# design.net
KiCad netlist of a schematic drawn in Altium Designer
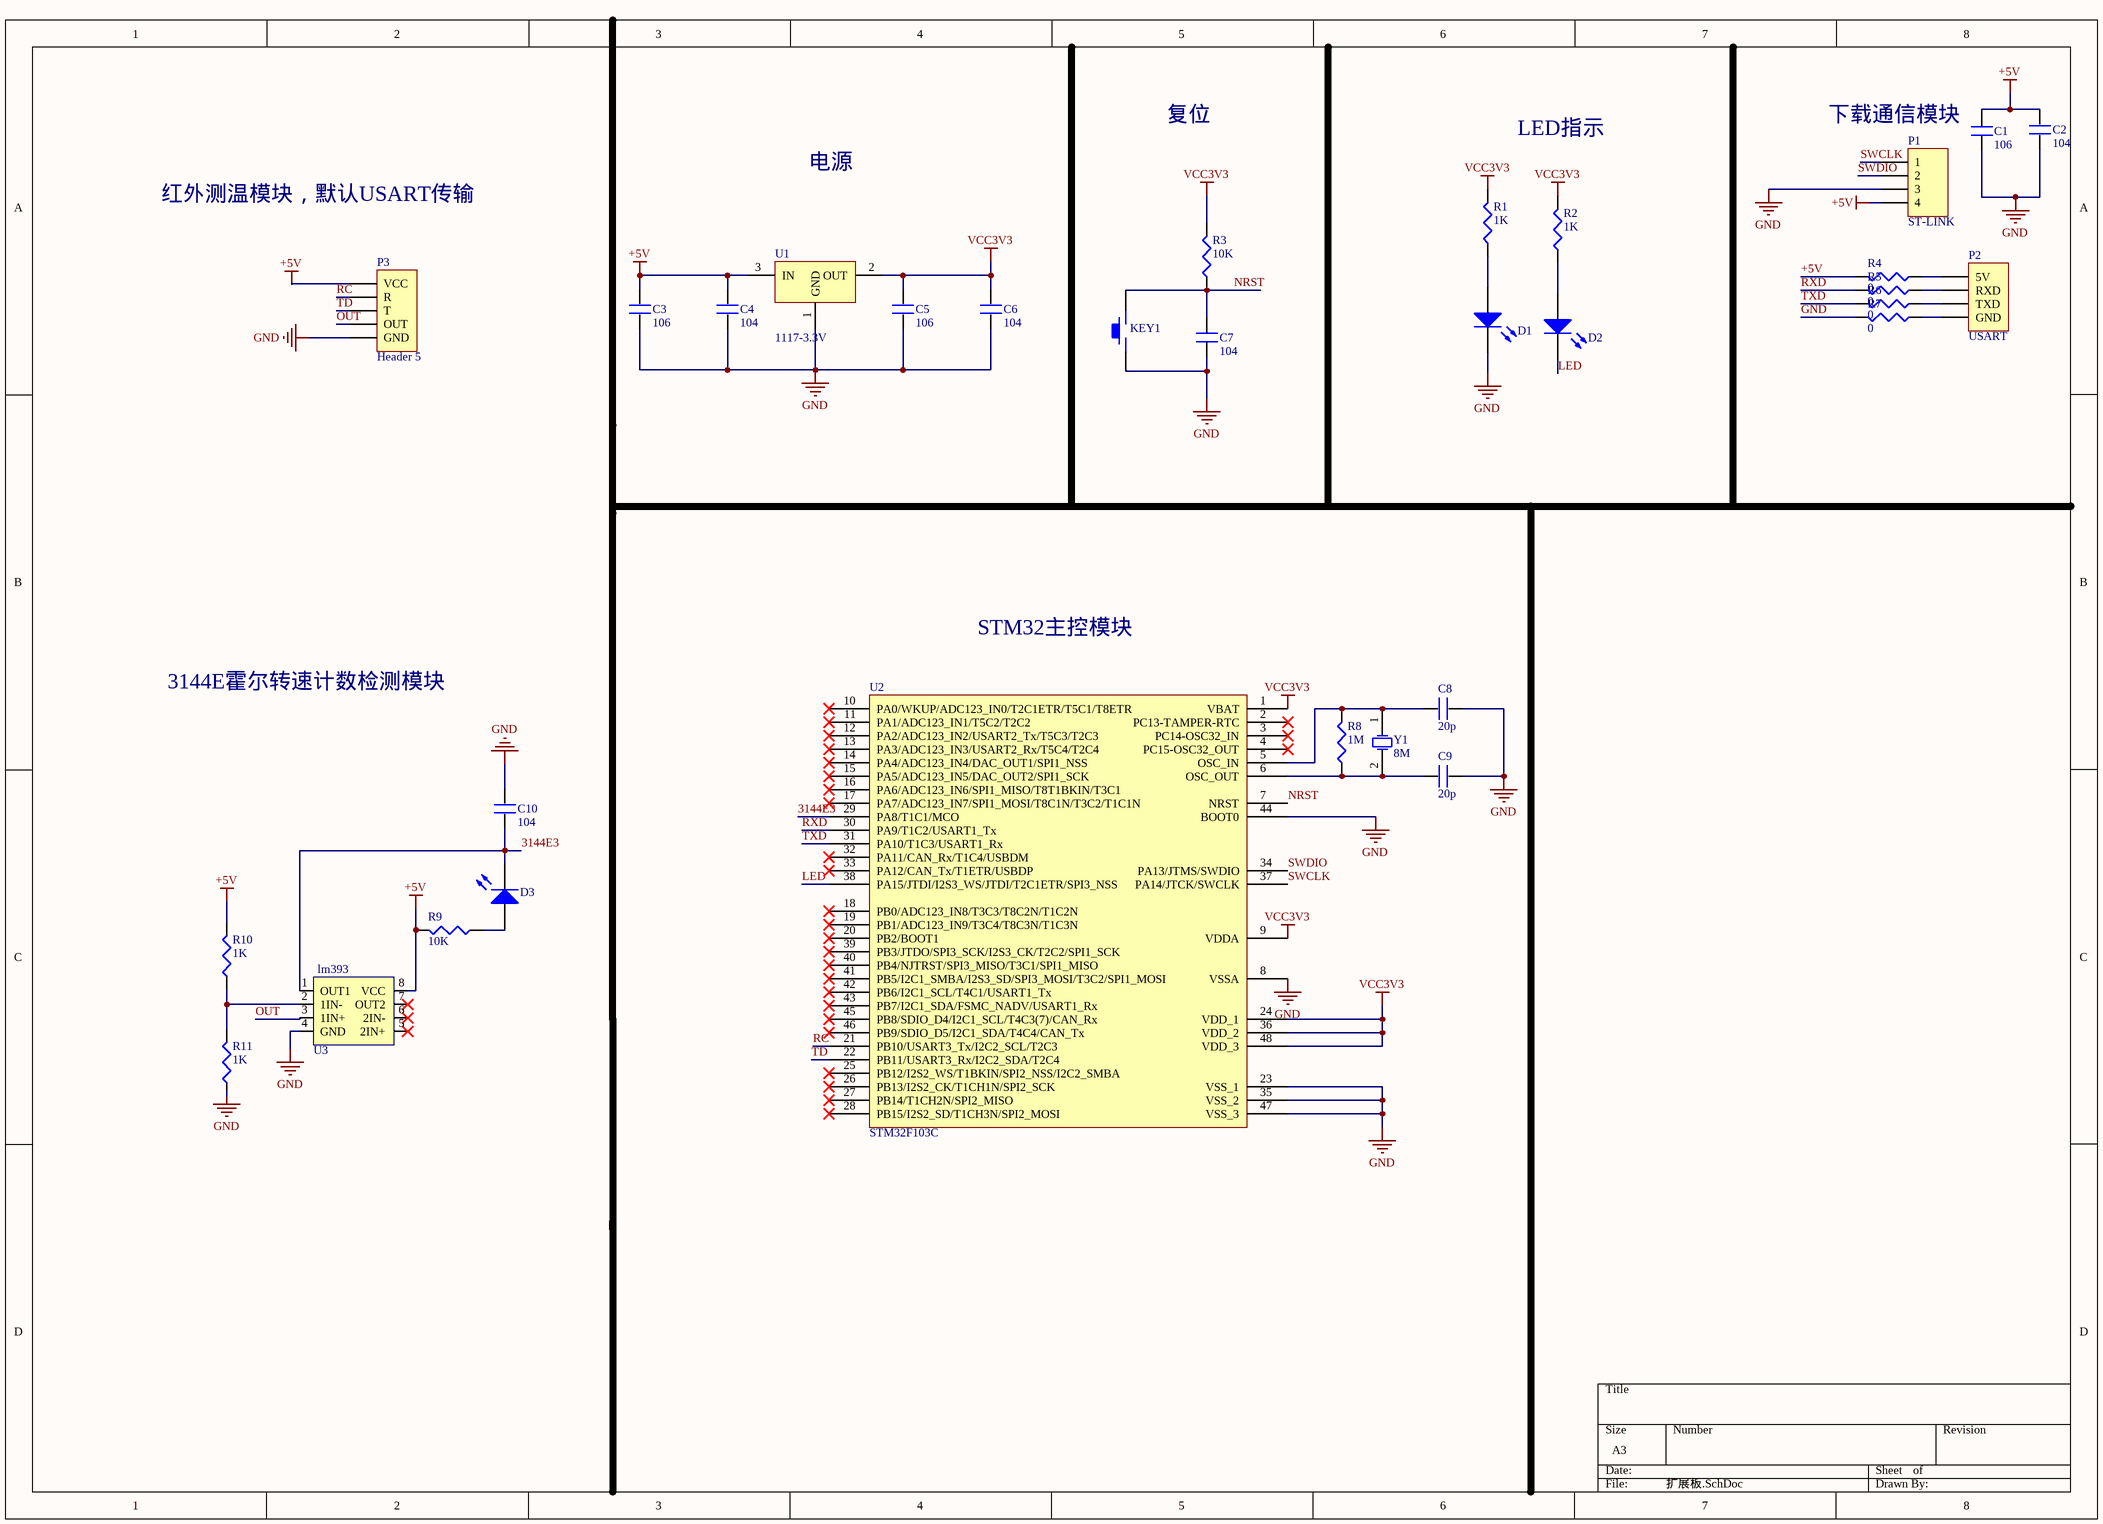
[diagram p0: 扩展板.SchDoc]

(export (version "E")
  (design (tool "Eeschema 10.0.6"))
  (components
    (comp (ref "C1")
      (value "106")
      (footprint "C0603(1608)")
      (libsource (lib "Uncle_Liu") (part "C_无极性_0603"))
    )
    (comp (ref "C2")
      (value "104")
      (footprint "C0603(1608)")
      (libsource (lib "Uncle_Liu") (part "C_无极性_0603"))
    )
    (comp (ref "C3")
      (value "106")
      (footprint "C0603(1608)")
      (libsource (lib "Uncle_Liu") (part "C_无极性_0603"))
    )
    (comp (ref "C4")
      (value "104")
      (footprint "C0603(1608)")
      (libsource (lib "Uncle_Liu") (part "C_无极性_0603"))
    )
    (comp (ref "C5")
      (value "106")
      (footprint "C0603(1608)")
      (libsource (lib "Uncle_Liu") (part "C_无极性_0603"))
    )
    (comp (ref "C6")
      (value "104")
      (footprint "C0603(1608)")
      (libsource (lib "Uncle_Liu") (part "C_无极性_0603"))
    )
    (comp (ref "C7")
      (value "104")
      (footprint "C0603(1608)")
      (libsource (lib "Uncle_Liu") (part "C_无极性_0603"))
    )
    (comp (ref "C8")
      (value "20p")
      (footprint "C0603(1608)")
      (libsource (lib "Uncle_Liu") (part "C_无极性_0603"))
    )
    (comp (ref "C9")
      (value "20p")
      (footprint "C0603(1608)")
      (libsource (lib "Uncle_Liu") (part "C_无极性_0603"))
    )
    (comp (ref "C10")
      (value "104")
      (footprint "C0603(1608)")
      (libsource (lib "Uncle_Liu") (part "C_无极性_0603"))
    )
    (comp (ref "D1")
      (value "LED0603")
      (footprint "LED_0805")
      (description "发光二极管")
      (fields (field (name "PUBLISHER") "Altium Limited"))
      (libsource (lib "Uncle_Liu") (part "LED0603"))
    )
    (comp (ref "D2")
      (value "LED0603")
      (footprint "LED_0805")
      (description "发光二极管")
      (fields (field (name "PUBLISHER") "Altium Limited"))
      (libsource (lib "Uncle_Liu") (part "LED0603"))
    )
    (comp (ref "D3")
      (value "LED0603")
      (footprint "LED_0805")
      (description "发光二极管")
      (fields (field (name "PUBLISHER") "Altium Limited"))
      (libsource (lib "Uncle_Liu") (part "LED0603"))
    )
    (comp (ref "KEY1") (value "KEY_M") (footprint "贴片按键") (libsource (lib "Uncle_Liu") (part "KEY_M")))
    (comp (ref "P1")
      (value "ST-LINK")
      (footprint "HDR1X4")
      (description "Header, 4-Pin")
      (fields (field (name "PUBLISHER") "Altium Limited"))
      (libsource (lib "Miscellaneous Connectors") (part "Header 4"))
    )
    (comp (ref "P2")
      (value "USART")
      (footprint "HDR1X4")
      (description "Header, 4-Pin")
      (fields (field (name "PUBLISHER") "Altium Limited"))
      (libsource (lib "Miscellaneous Connectors") (part "Header 4"))
    )
    (comp (ref "P3")
      (value "Header 5")
      (footprint "HDR1X5")
      (description "Header, 5-Pin")
      (fields (field (name "PUBLISHER") "Altium Limited"))
      (libsource (lib "Miscellaneous Connectors") (part "Header 5"))
    )
    (comp (ref "R1")
      (value "1K")
      (footprint "J1-0603")
      (description "Resistor")
      (fields (field (name "PUBLISHER") "Altium Limited"))
      (libsource (lib "Miscellaneous Devices") (part "Res3"))
    )
    (comp (ref "R2")
      (value "1K")
      (footprint "J1-0603")
      (description "Resistor")
      (fields (field (name "PUBLISHER") "Altium Limited"))
      (libsource (lib "Miscellaneous Devices") (part "Res3"))
    )
    (comp (ref "R3")
      (value "10K")
      (footprint "J1-0603")
      (description "Resistor")
      (fields (field (name "PUBLISHER") "Altium Limited"))
      (libsource (lib "Miscellaneous Devices") (part "Res3"))
    )
    (comp (ref "R4")
      (value "0")
      (footprint "J1-0603")
      (description "Resistor")
      (fields (field (name "PUBLISHER") "Altium Limited"))
      (libsource (lib "Miscellaneous Devices") (part "Res3"))
    )
    (comp (ref "R5")
      (value "0")
      (footprint "J1-0603")
      (description "Resistor")
      (fields (field (name "PUBLISHER") "Altium Limited"))
      (libsource (lib "Miscellaneous Devices") (part "Res3"))
    )
    (comp (ref "R6")
      (value "0")
      (footprint "J1-0603")
      (description "Resistor")
      (fields (field (name "PUBLISHER") "Altium Limited"))
      (libsource (lib "Miscellaneous Devices") (part "Res3"))
    )
    (comp (ref "R7")
      (value "0")
      (footprint "J1-0603")
      (description "Resistor")
      (fields (field (name "PUBLISHER") "Altium Limited"))
      (libsource (lib "Miscellaneous Devices") (part "Res3"))
    )
    (comp (ref "R8")
      (value "1M")
      (footprint "J1-0603")
      (description "Resistor")
      (fields (field (name "PUBLISHER") "Altium Limited"))
      (libsource (lib "Miscellaneous Devices") (part "Res3"))
    )
    (comp (ref "R9")
      (value "10K")
      (footprint "J1-0603")
      (description "Resistor")
      (fields (field (name "PUBLISHER") "Altium Limited"))
      (libsource (lib "Miscellaneous Devices") (part "Res3"))
    )
    (comp (ref "R10")
      (value "1K")
      (footprint "J1-0603")
      (description "Resistor")
      (fields (field (name "PUBLISHER") "Altium Limited"))
      (libsource (lib "Miscellaneous Devices") (part "Res3"))
    )
    (comp (ref "R11")
      (value "1K")
      (footprint "J1-0603")
      (description "Resistor")
      (fields (field (name "PUBLISHER") "Altium Limited"))
      (libsource (lib "Miscellaneous Devices") (part "Res3"))
    )
    (comp (ref "U1")
      (value "1117-3.3V")
      (footprint "SOT-223")
      (description "xA 3.3V")
      (fields (field (name "PUBLISHER") "Altium Limited"))
      (libsource (lib "扩展板") (part "1117-3.3V"))
    )
    (comp (ref "U2")
      (value "STM32F103C")
      (footprint "LQFP-48_7x7x05P")
      (description "STM32单片机48引脚")
      (libsource (lib "Uncle_Liu") (part "STM32F103C"))
    )
    (comp (ref "U3") (value "lm393") (footprint "SOP-8_150mil") (libsource (lib "Uncle_Liu") (part "lm393")))
    (comp (ref "Y1")
      (value "8M")
      (footprint "XTAL-HC49US2")
      (description "Crystal Oscillator")
      (fields (field (name "PUBLISHER") "Altium Limited"))
      (libsource (lib "Miscellaneous Devices") (part "XTAL"))
    )
  )
  (nets
    (net (code "1") (name "+5V") (class "Default")
      (node (ref "C1") (pin "2") (pintype "passive"))
      (node (ref "C2") (pin "2") (pintype "passive"))
      (node (ref "C3") (pin "2") (pintype "passive"))
      (node (ref "C4") (pin "2") (pintype "passive"))
      (node (ref "P1") (pin "4") (pinfunction "GND_4") (pintype "passive"))
      (node (ref "P3") (pin "1") (pinfunction "VCC_1") (pintype "passive"))
      (node (ref "R10") (pin "2") (pinfunction "2_2") (pintype "passive"))
      (node (ref "R4") (pin "2") (pinfunction "2_2") (pintype "passive"))
      (node (ref "R9") (pin "2") (pinfunction "2_2") (pintype "passive"))
      (node (ref "U1") (pin "3") (pinfunction "IN_3") (pintype "power_in"))
      (node (ref "U3") (pin "8") (pinfunction "VCC_8") (pintype "passive"))
    )
    (net (code "2") (name "/3144E3") (class "Default")
      (node (ref "C10") (pin "1") (pintype "passive"))
      (node (ref "D3") (pin "2") (pinfunction "K_2") (pintype "passive"))
      (node (ref "U2") (pin "29") (pinfunction "PA8/T1C1/MCO_29") (pintype "passive"))
      (node (ref "U3") (pin "1") (pinfunction "OUT1_1") (pintype "passive"))
    )
    (net (code "3") (name "/LED") (class "Default")
      (node (ref "D2") (pin "2") (pinfunction "K_2") (pintype "passive"))
      (node (ref "U2") (pin "38") (pinfunction "PA15/JTDI/I2S3_WS/JTDI/T2C1ETR/SPI3_NSS_38") (pintype "passive"))
    )
    (net (code "4") (name "/NRST") (class "Default")
      (node (ref "C7") (pin "2") (pintype "passive"))
      (node (ref "KEY1") (pin "2") (pinfunction "2_2") (pintype "passive"))
      (node (ref "R3") (pin "1") (pinfunction "1_1") (pintype "passive"))
      (node (ref "U2") (pin "7") (pinfunction "NRST_7") (pintype "passive"))
    )
    (net (code "5") (name "/OUT") (class "Default")
      (node (ref "P3") (pin "4") (pinfunction "OUT_4") (pintype "passive"))
      (node (ref "U3") (pin "3") (pinfunction "1IN+_3") (pintype "passive"))
    )
    (net (code "6") (name "/RC") (class "Default")
      (node (ref "P3") (pin "2") (pinfunction "R_2") (pintype "passive"))
      (node (ref "U2") (pin "21") (pinfunction "PB10/USART3_Tx/I2C2_SCL/T2C3_21") (pintype "passive"))
    )
    (net (code "7") (name "/RXD") (class "Default")
      (node (ref "R5") (pin "2") (pinfunction "2_2") (pintype "passive"))
      (node (ref "U2") (pin "30") (pinfunction "PA9/T1C2/USART1_Tx_30") (pintype "passive"))
    )
    (net (code "8") (name "/SWCLK") (class "Default")
      (node (ref "P1") (pin "1") (pinfunction "5V_1") (pintype "passive"))
      (node (ref "U2") (pin "37") (pinfunction "PA14/JTCK/SWCLK_37") (pintype "passive"))
    )
    (net (code "9") (name "/SWDIO") (class "Default")
      (node (ref "P1") (pin "2") (pinfunction "RXD_2") (pintype "passive"))
      (node (ref "U2") (pin "34") (pinfunction "PA13/JTMS/SWDIO_34") (pintype "passive"))
    )
    (net (code "10") (name "/TD") (class "Default")
      (node (ref "P3") (pin "3") (pinfunction "T_3") (pintype "passive"))
      (node (ref "U2") (pin "22") (pinfunction "PB11/USART3_Rx/I2C2_SDA/T2C4_22") (pintype "passive"))
    )
    (net (code "11") (name "/TXD") (class "Default")
      (node (ref "R6") (pin "2") (pinfunction "2_2") (pintype "passive"))
      (node (ref "U2") (pin "31") (pinfunction "PA10/T1C3/USART1_Rx_31") (pintype "passive"))
    )
    (net (code "12") (name "GND") (class "Default")
      (node (ref "C1") (pin "1") (pintype "passive"))
      (node (ref "C10") (pin "2") (pintype "passive"))
      (node (ref "C2") (pin "1") (pintype "passive"))
      (node (ref "C3") (pin "1") (pintype "passive"))
      (node (ref "C4") (pin "1") (pintype "passive"))
      (node (ref "C5") (pin "1") (pintype "passive"))
      (node (ref "C6") (pin "1") (pintype "passive"))
      (node (ref "C7") (pin "1") (pintype "passive"))
      (node (ref "C8") (pin "1") (pintype "passive"))
      (node (ref "C9") (pin "1") (pintype "passive"))
      (node (ref "D1") (pin "2") (pinfunction "K_2") (pintype "passive"))
      (node (ref "KEY1") (pin "1") (pinfunction "1_1") (pintype "passive"))
      (node (ref "P1") (pin "3") (pinfunction "TXD_3") (pintype "passive"))
      (node (ref "P3") (pin "5") (pinfunction "GND_5") (pintype "passive"))
      (node (ref "R11") (pin "1") (pinfunction "1_1") (pintype "passive"))
      (node (ref "R7") (pin "2") (pinfunction "2_2") (pintype "passive"))
      (node (ref "U1") (pin "1") (pinfunction "GND_1") (pintype "power_in"))
      (node (ref "U2") (pin "23") (pinfunction "VSS_1_23") (pintype "passive"))
      (node (ref "U2") (pin "35") (pinfunction "VSS_2_35") (pintype "passive"))
      (node (ref "U2") (pin "44") (pinfunction "BOOT0_44") (pintype "passive"))
      (node (ref "U2") (pin "47") (pinfunction "VSS_3_47") (pintype "passive"))
      (node (ref "U2") (pin "8") (pinfunction "VSSA_8") (pintype "passive"))
      (node (ref "U3") (pin "4") (pinfunction "GND_4") (pintype "passive"))
    )
    (net (code "13") (name "Net-(D1-A)") (class "Default")
      (node (ref "D1") (pin "1") (pinfunction "A_1") (pintype "passive"))
      (node (ref "R1") (pin "1") (pinfunction "1_1") (pintype "passive"))
    )
    (net (code "14") (name "Net-(D2-A)") (class "Default")
      (node (ref "D2") (pin "1") (pinfunction "A_1") (pintype "passive"))
      (node (ref "R2") (pin "1") (pinfunction "1_1") (pintype "passive"))
    )
    (net (code "15") (name "Net-(D3-A)") (class "Default")
      (node (ref "D3") (pin "1") (pinfunction "A_1") (pintype "passive"))
      (node (ref "R9") (pin "1") (pinfunction "1_1") (pintype "passive"))
    )
    (net (code "16") (name "Net-(P2-5V)") (class "Default")
      (node (ref "P2") (pin "1") (pinfunction "5V_1") (pintype "passive"))
      (node (ref "R4") (pin "1") (pinfunction "1_1") (pintype "passive"))
    )
    (net (code "17") (name "Net-(P2-GND)") (class "Default")
      (node (ref "P2") (pin "4") (pinfunction "GND_4") (pintype "passive"))
      (node (ref "R7") (pin "1") (pinfunction "1_1") (pintype "passive"))
    )
    (net (code "18") (name "Net-(P2-RXD)") (class "Default")
      (node (ref "P2") (pin "2") (pinfunction "RXD_2") (pintype "passive"))
      (node (ref "R5") (pin "1") (pinfunction "1_1") (pintype "passive"))
    )
    (net (code "19") (name "Net-(P2-TXD)") (class "Default")
      (node (ref "P2") (pin "3") (pinfunction "TXD_3") (pintype "passive"))
      (node (ref "R6") (pin "1") (pinfunction "1_1") (pintype "passive"))
    )
    (net (code "20") (name "Net-(U2-OSC_IN)") (class "Default")
      (node (ref "C8") (pin "2") (pintype "passive"))
      (node (ref "R8") (pin "2") (pinfunction "2_2") (pintype "passive"))
      (node (ref "U2") (pin "5") (pinfunction "OSC_IN_5") (pintype "passive"))
      (node (ref "Y1") (pin "1") (pinfunction "OSC1_1") (pintype "passive"))
    )
    (net (code "21") (name "Net-(U2-OSC_OUT)") (class "Default")
      (node (ref "C9") (pin "2") (pintype "passive"))
      (node (ref "R8") (pin "1") (pinfunction "1_1") (pintype "passive"))
      (node (ref "U2") (pin "6") (pinfunction "OSC_OUT_6") (pintype "passive"))
      (node (ref "Y1") (pin "2") (pinfunction "OSC2_2") (pintype "passive"))
    )
    (net (code "22") (name "Net-(U3-1IN-)") (class "Default")
      (node (ref "R10") (pin "1") (pinfunction "1_1") (pintype "passive"))
      (node (ref "R11") (pin "2") (pinfunction "2_2") (pintype "passive"))
      (node (ref "U3") (pin "2") (pinfunction "1IN-_2") (pintype "passive"))
    )
    (net (code "23") (name "VCC3V3") (class "Default")
      (node (ref "C5") (pin "2") (pintype "passive"))
      (node (ref "C6") (pin "2") (pintype "passive"))
      (node (ref "R1") (pin "2") (pinfunction "2_2") (pintype "passive"))
      (node (ref "R2") (pin "2") (pinfunction "2_2") (pintype "passive"))
      (node (ref "R3") (pin "2") (pinfunction "2_2") (pintype "passive"))
      (node (ref "U1") (pin "2") (pinfunction "OUT_2") (pintype "power_in"))
      (node (ref "U2") (pin "1") (pinfunction "VBAT_1") (pintype "passive"))
      (node (ref "U2") (pin "24") (pinfunction "VDD_1_24") (pintype "passive"))
      (node (ref "U2") (pin "36") (pinfunction "VDD_2_36") (pintype "passive"))
      (node (ref "U2") (pin "48") (pinfunction "VDD_3_48") (pintype "passive"))
      (node (ref "U2") (pin "9") (pinfunction "VDDA_9") (pintype "passive"))
    )
    (net (code "24") (name "unconnected-(U2-PA0{slash}WKUP{slash}ADC123_IN0{slash}T2C1ETR{slash}T5C1{slash}T8ETR-Pad10)") (class "Default")
      (node (ref "U2") (pin "10") (pinfunction "PA0/WKUP/ADC123_IN0/T2C1ETR/T5C1/T8ETR_10") (pintype "passive+no_connect"))
    )
    (net (code "25") (name "unconnected-(U2-PA1{slash}ADC123_IN1{slash}T5C2{slash}T2C2-Pad11)") (class "Default")
      (node (ref "U2") (pin "11") (pinfunction "PA1/ADC123_IN1/T5C2/T2C2_11") (pintype "passive+no_connect"))
    )
    (net (code "26") (name "unconnected-(U2-PA2{slash}ADC123_IN2{slash}USART2_Tx{slash}T5C3{slash}T2C3-Pad12)") (class "Default")
      (node (ref "U2") (pin "12") (pinfunction "PA2/ADC123_IN2/USART2_Tx/T5C3/T2C3_12") (pintype "passive+no_connect"))
    )
    (net (code "27") (name "unconnected-(U2-PA3{slash}ADC123_IN3{slash}USART2_Rx{slash}T5C4{slash}T2C4-Pad13)") (class "Default")
      (node (ref "U2") (pin "13") (pinfunction "PA3/ADC123_IN3/USART2_Rx/T5C4/T2C4_13") (pintype "passive+no_connect"))
    )
    (net (code "28") (name "unconnected-(U2-PA4{slash}ADC123_IN4{slash}DAC_OUT1{slash}SPI1_NSS-Pad14)") (class "Default")
      (node (ref "U2") (pin "14") (pinfunction "PA4/ADC123_IN4/DAC_OUT1/SPI1_NSS_14") (pintype "passive+no_connect"))
    )
    (net (code "29") (name "unconnected-(U2-PA5{slash}ADC123_IN5{slash}DAC_OUT2{slash}SPI1_SCK-Pad15)") (class "Default")
      (node (ref "U2") (pin "15") (pinfunction "PA5/ADC123_IN5/DAC_OUT2/SPI1_SCK_15") (pintype "passive+no_connect"))
    )
    (net (code "30") (name "unconnected-(U2-PA6{slash}ADC123_IN6{slash}SPI1_MISO{slash}T8T1BKIN{slash}T3C1-Pad16)") (class "Default")
      (node (ref "U2") (pin "16") (pinfunction "PA6/ADC123_IN6/SPI1_MISO/T8T1BKIN/T3C1_16") (pintype "passive+no_connect"))
    )
    (net (code "31") (name "unconnected-(U2-PA7{slash}ADC123_IN7{slash}SPI1_MOSI{slash}T8C1N{slash}T3C2{slash}T1C1N-Pad17)") (class "Default")
      (node (ref "U2") (pin "17") (pinfunction "PA7/ADC123_IN7/SPI1_MOSI/T8C1N/T3C2/T1C1N_17") (pintype "passive+no_connect"))
    )
    (net (code "32") (name "unconnected-(U2-PA11{slash}CAN_Rx{slash}T1C4{slash}USBDM-Pad32)") (class "Default")
      (node (ref "U2") (pin "32") (pinfunction "PA11/CAN_Rx/T1C4/USBDM_32") (pintype "passive+no_connect"))
    )
    (net (code "33") (name "unconnected-(U2-PA12{slash}CAN_Tx{slash}T1ETR{slash}USBDP-Pad33)") (class "Default")
      (node (ref "U2") (pin "33") (pinfunction "PA12/CAN_Tx/T1ETR/USBDP_33") (pintype "passive+no_connect"))
    )
    (net (code "34") (name "unconnected-(U2-PB0{slash}ADC123_IN8{slash}T3C3{slash}T8C2N{slash}T1C2N-Pad18)") (class "Default")
      (node (ref "U2") (pin "18") (pinfunction "PB0/ADC123_IN8/T3C3/T8C2N/T1C2N_18") (pintype "passive+no_connect"))
    )
    (net (code "35") (name "unconnected-(U2-PB1{slash}ADC123_IN9{slash}T3C4{slash}T8C3N{slash}T1C3N-Pad19)") (class "Default")
      (node (ref "U2") (pin "19") (pinfunction "PB1/ADC123_IN9/T3C4/T8C3N/T1C3N_19") (pintype "passive+no_connect"))
    )
    (net (code "36") (name "unconnected-(U2-PB2{slash}BOOT1-Pad20)") (class "Default")
      (node (ref "U2") (pin "20") (pinfunction "PB2/BOOT1_20") (pintype "passive+no_connect"))
    )
    (net (code "37") (name "unconnected-(U2-PB3{slash}JTDO{slash}SPI3_SCK{slash}I2S3_CK{slash}T2C2{slash}SPI1_SCK-Pad39)") (class "Default")
      (node (ref "U2") (pin "39") (pinfunction "PB3/JTDO/SPI3_SCK/I2S3_CK/T2C2/SPI1_SCK_39") (pintype "passive+no_connect"))
    )
    (net (code "38") (name "unconnected-(U2-PB4{slash}NJTRST{slash}SPI3_MISO{slash}T3C1{slash}SPI1_MISO-Pad40)") (class "Default")
      (node (ref "U2") (pin "40") (pinfunction "PB4/NJTRST/SPI3_MISO/T3C1/SPI1_MISO_40") (pintype "passive+no_connect"))
    )
    (net (code "39") (name "unconnected-(U2-PB5{slash}I2C1_SMBA{slash}I2S3_SD{slash}SPI3_MOSI{slash}T3C2{slash}SPI1_MOSI-Pad41)") (class "Default")
      (node (ref "U2") (pin "41") (pinfunction "PB5/I2C1_SMBA/I2S3_SD/SPI3_MOSI/T3C2/SPI1_MOSI_41") (pintype "passive+no_connect"))
    )
    (net (code "40") (name "unconnected-(U2-PB6{slash}I2C1_SCL{slash}T4C1{slash}USART1_Tx-Pad42)") (class "Default")
      (node (ref "U2") (pin "42") (pinfunction "PB6/I2C1_SCL/T4C1/USART1_Tx_42") (pintype "passive+no_connect"))
    )
    (net (code "41") (name "unconnected-(U2-PB7{slash}I2C1_SDA{slash}FSMC_NADV{slash}USART1_Rx-Pad43)") (class "Default")
      (node (ref "U2") (pin "43") (pinfunction "PB7/I2C1_SDA/FSMC_NADV/USART1_Rx_43") (pintype "passive+no_connect"))
    )
    (net (code "42") (name "unconnected-(U2-PB8{slash}SDIO_D4{slash}I2C1_SCL{slash}T4C3(7){slash}CAN_Rx-Pad45)") (class "Default")
      (node (ref "U2") (pin "45") (pinfunction "PB8/SDIO_D4/I2C1_SCL/T4C3(7)/CAN_Rx_45") (pintype "passive+no_connect"))
    )
    (net (code "43") (name "unconnected-(U2-PB9{slash}SDIO_D5{slash}I2C1_SDA{slash}T4C4{slash}CAN_Tx-Pad46)") (class "Default")
      (node (ref "U2") (pin "46") (pinfunction "PB9/SDIO_D5/I2C1_SDA/T4C4/CAN_Tx_46") (pintype "passive+no_connect"))
    )
    (net (code "44") (name "unconnected-(U2-PB12{slash}I2S2_WS{slash}T1BKIN{slash}SPI2_NSS{slash}I2C2_SMBA-Pad25)") (class "Default")
      (node (ref "U2") (pin "25") (pinfunction "PB12/I2S2_WS/T1BKIN/SPI2_NSS/I2C2_SMBA_25") (pintype "passive+no_connect"))
    )
    (net (code "45") (name "unconnected-(U2-PB13{slash}I2S2_CK{slash}T1CH1N{slash}SPI2_SCK-Pad26)") (class "Default")
      (node (ref "U2") (pin "26") (pinfunction "PB13/I2S2_CK/T1CH1N/SPI2_SCK_26") (pintype "passive+no_connect"))
    )
    (net (code "46") (name "unconnected-(U2-PB14{slash}T1CH2N{slash}SPI2_MISO-Pad27)") (class "Default")
      (node (ref "U2") (pin "27") (pinfunction "PB14/T1CH2N/SPI2_MISO_27") (pintype "passive+no_connect"))
    )
    (net (code "47") (name "unconnected-(U2-PB15{slash}I2S2_SD{slash}T1CH3N{slash}SPI2_MOSI-Pad28)") (class "Default")
      (node (ref "U2") (pin "28") (pinfunction "PB15/I2S2_SD/T1CH3N/SPI2_MOSI_28") (pintype "passive+no_connect"))
    )
    (net (code "48") (name "unconnected-(U2-PC13-TAMPER-RTC-Pad2)") (class "Default")
      (node (ref "U2") (pin "2") (pinfunction "PC13-TAMPER-RTC_2") (pintype "passive+no_connect"))
    )
    (net (code "49") (name "unconnected-(U2-PC14-OSC32_IN-Pad3)") (class "Default")
      (node (ref "U2") (pin "3") (pinfunction "PC14-OSC32_IN_3") (pintype "passive+no_connect"))
    )
    (net (code "50") (name "unconnected-(U2-PC15-OSC32_OUT-Pad4)") (class "Default")
      (node (ref "U2") (pin "4") (pinfunction "PC15-OSC32_OUT_4") (pintype "passive+no_connect"))
    )
    (net (code "51") (name "unconnected-(U3-2IN+-Pad5)") (class "Default")
      (node (ref "U3") (pin "5") (pinfunction "2IN+_5") (pintype "passive+no_connect"))
    )
    (net (code "52") (name "unconnected-(U3-2IN--Pad6)") (class "Default")
      (node (ref "U3") (pin "6") (pinfunction "2IN-_6") (pintype "passive+no_connect"))
    )
    (net (code "53") (name "unconnected-(U3-OUT2-Pad7)") (class "Default")
      (node (ref "U3") (pin "7") (pinfunction "OUT2_7") (pintype "passive+no_connect"))
    )
  )
)
